# Protocell_module.net
KiCad netlist of a schematic drawn in EAGLE
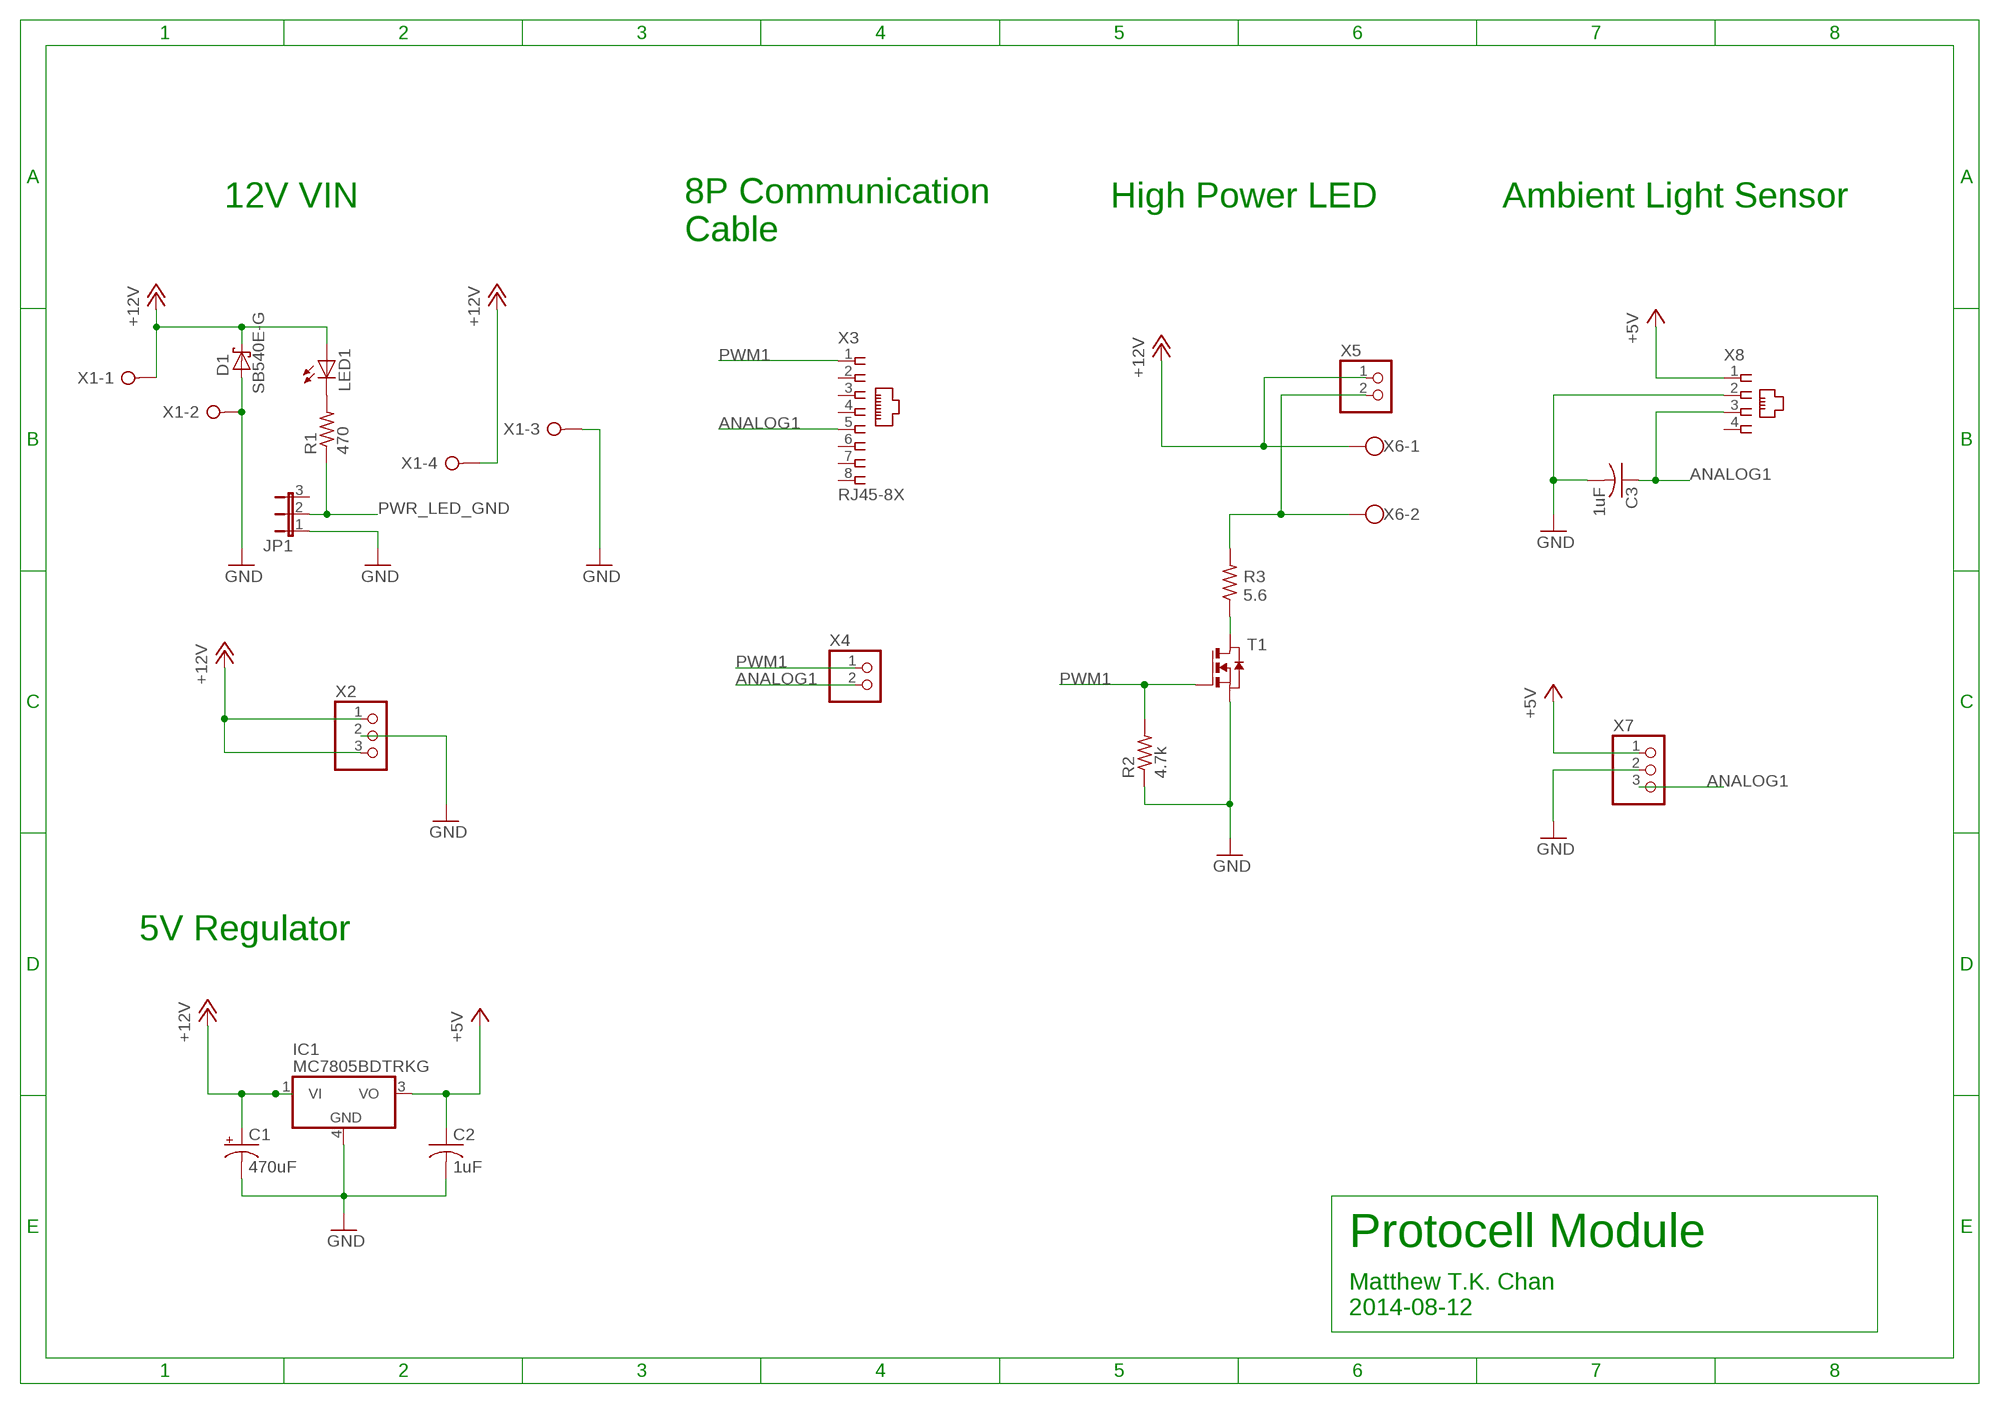
[diagram p0: schematic, sheet 1]

(export (version "E")
  (design (tool "Eeschema 10.0.6"))
  (components
    (comp (ref "C1")
      (value "470uF")
      (footprint "eagle-import:E5-10,5")
      (libsource (lib "eagle-import") (part "CPOL-USE5-10.5"))
    )
    (comp (ref "C2")
      (value "1uF")
      (footprint "eagle-import:C0603")
      (libsource (lib "eagle-import") (part "C-USC0603"))
    )
    (comp (ref "C3")
      (value "1uF")
      (footprint "eagle-import:C0603")
      (libsource (lib "eagle-import") (part "C-USC0603"))
    )
    (comp (ref "D1")
      (value "SB540E-G")
      (footprint "eagle-import:DO201T15")
      (libsource (lib "eagle-import") (part "SB540E-G"))
    )
    (comp (ref "IC1")
      (value "MC7805BDTRKG")
      (footprint "eagle-import:DPACK_3")
      (libsource (lib "eagle-import") (part "MC7805BDTRKG"))
    )
    (comp (ref "JP1")
      (value "JP2E")
      (footprint "eagle-import:JP2")
      (libsource (lib "eagle-import") (part "JP2E"))
    )
    (comp (ref "LED1")
      (value "LEDSML1206")
      (footprint "eagle-import:SML1206")
      (libsource (lib "eagle-import") (part "LEDSML1206"))
    )
    (comp (ref "R1")
      (value "470")
      (footprint "eagle-import:R0603")
      (libsource (lib "eagle-import") (part "R-US_R0603"))
    )
    (comp (ref "R2")
      (value "4.7k")
      (footprint "eagle-import:R0603")
      (libsource (lib "eagle-import") (part "R-US_R0603"))
    )
    (comp (ref "R3")
      (value "5.6")
      (footprint "eagle-import:YAGEO_SQP500JB")
      (libsource (lib "eagle-import") (part "SQP500JB-5R6"))
    )
    (comp (ref "T1")
      (value "NTD5867NLT4G")
      (footprint "eagle-import:DPACK")
      (libsource (lib "eagle-import") (part "NTD5867NLT4G"))
    )
    (comp (ref "X1")
      (value "W237-04P")
      (footprint "eagle-import:W237-4P")
      (libsource (lib "eagle-import") (part "W237-04P"))
    )
    (comp (ref "X2")
      (value "PINHD-1X3/90")
      (footprint "eagle-import:1X03_90")
      (libsource (lib "eagle-import") (part "PINHD-1X3/90"))
    )
    (comp (ref "X3")
      (value "RJ45-8X")
      (footprint "eagle-import:RJ45-NO-SHIELD")
      (libsource (lib "eagle-import") (part "RJ45-8X"))
    )
    (comp (ref "X4")
      (value "PINHD-1X2/90")
      (footprint "eagle-import:1X02_90")
      (libsource (lib "eagle-import") (part "PINHD-1X2/90"))
    )
    (comp (ref "X5")
      (value "PINHD-1X2/90")
      (footprint "eagle-import:1X02_90")
      (libsource (lib "eagle-import") (part "PINHD-1X2/90"))
    )
    (comp (ref "X6")
      (value "W237-102")
      (footprint "eagle-import:W237-102")
      (fields (field (name "MPN") "237-102"))
      (libsource (lib "eagle-import") (part "W237-102"))
    )
    (comp (ref "X7")
      (value "PINHD-1X3/90")
      (footprint "eagle-import:1X03_90")
      (libsource (lib "eagle-import") (part "PINHD-1X3/90"))
    )
    (comp (ref "X8")
      (value "558872-1")
      (footprint "eagle-import:558872-1")
      (fields (field (name "MF") "TYCO ELECTRONICS") (field (name "MPN") "5558872-1"))
      (libsource (lib "eagle-import") (part "558872-1"))
    )
  )
  (nets
    (net (code "1") (name "+5V") (class "Default")
      (node (ref "C2") (pin "1") (pinfunction "1_1") (pintype "passive"))
      (node (ref "IC1") (pin "3") (pinfunction "VO_3") (pintype "passive"))
      (node (ref "X7") (pin "1") (pinfunction "1_1") (pintype "passive"))
      (node (ref "X8") (pin "1") (pinfunction "1_1") (pintype "passive"))
    )
    (net (code "2") (name "+12V") (class "Default")
      (node (ref "C1") (pin "+") (pinfunction "+_+") (pintype "passive"))
      (node (ref "D1") (pin "C") (pinfunction "C_C") (pintype "passive"))
      (node (ref "IC1") (pin "1") (pinfunction "VI_1") (pintype "input"))
      (node (ref "LED1") (pin "A") (pinfunction "A_A") (pintype "passive"))
      (node (ref "X1") (pin "1") (pinfunction "KL_1") (pintype "passive"))
      (node (ref "X1") (pin "4") (pinfunction "KL_4") (pintype "passive"))
      (node (ref "X2") (pin "1") (pinfunction "1_1") (pintype "passive"))
      (node (ref "X2") (pin "3") (pinfunction "3_3") (pintype "passive"))
      (node (ref "X5") (pin "1") (pinfunction "1_1") (pintype "passive"))
      (node (ref "X6") (pin "1") (pinfunction "KL_1") (pintype "passive"))
    )
    (net (code "3") (name "/ANALOG1") (class "Default")
      (node (ref "C3") (pin "1") (pinfunction "1_1") (pintype "passive"))
      (node (ref "X3") (pin "5") (pinfunction "5_5") (pintype "passive"))
      (node (ref "X4") (pin "2") (pinfunction "2_2") (pintype "passive"))
      (node (ref "X7") (pin "3") (pinfunction "3_3") (pintype "passive"))
      (node (ref "X8") (pin "3") (pinfunction "3_3") (pintype "passive"))
    )
    (net (code "4") (name "/PWM1") (class "Default")
      (node (ref "R2") (pin "2") (pinfunction "2_2") (pintype "passive"))
      (node (ref "T1") (pin "1") (pinfunction "G_1") (pintype "passive"))
      (node (ref "X3") (pin "1") (pinfunction "1_1") (pintype "passive"))
      (node (ref "X4") (pin "1") (pinfunction "1_1") (pintype "passive"))
    )
    (net (code "5") (name "/PWR_LED_GND") (class "Default")
      (node (ref "JP1") (pin "2") (pinfunction "2_2") (pintype "passive"))
      (node (ref "R1") (pin "1") (pinfunction "1_1") (pintype "passive"))
    )
    (net (code "6") (name "GND") (class "Default")
      (node (ref "C1") (pin "-") (pinfunction "-_-") (pintype "passive"))
      (node (ref "C2") (pin "2") (pinfunction "2_2") (pintype "passive"))
      (node (ref "C3") (pin "2") (pinfunction "2_2") (pintype "passive"))
      (node (ref "D1") (pin "A") (pinfunction "A_A") (pintype "passive"))
      (node (ref "IC1") (pin "4") (pinfunction "GND_4") (pintype "passive"))
      (node (ref "JP1") (pin "1") (pinfunction "1_1") (pintype "passive"))
      (node (ref "R2") (pin "1") (pinfunction "1_1") (pintype "passive"))
      (node (ref "T1") (pin "3") (pinfunction "S_3") (pintype "passive"))
      (node (ref "X1") (pin "2") (pinfunction "KL_2") (pintype "passive"))
      (node (ref "X1") (pin "3") (pinfunction "KL_3") (pintype "passive"))
      (node (ref "X2") (pin "2") (pinfunction "2_2") (pintype "passive"))
      (node (ref "X7") (pin "2") (pinfunction "2_2") (pintype "passive"))
      (node (ref "X8") (pin "2") (pinfunction "2_2") (pintype "passive"))
    )
    (net (code "7") (name "Net-(LED1-PadC)") (class "Default")
      (node (ref "LED1") (pin "C") (pinfunction "C_C") (pintype "passive"))
      (node (ref "R1") (pin "2") (pinfunction "2_2") (pintype "passive"))
    )
    (net (code "8") (name "Net-(T1-D)") (class "Default")
      (node (ref "R3") (pin "1") (pinfunction "1_1") (pintype "passive"))
      (node (ref "T1") (pin "2") (pinfunction "D_2") (pintype "passive"))
    )
    (net (code "9") (name "Net-(X6B-KL)") (class "Default")
      (node (ref "R3") (pin "2") (pinfunction "2_2") (pintype "passive"))
      (node (ref "X5") (pin "2") (pinfunction "2_2") (pintype "passive"))
      (node (ref "X6") (pin "2") (pinfunction "KL_2") (pintype "passive"))
    )
    (net (code "10") (name "unconnected-(JP1-Pad3)") (class "Default")
      (node (ref "JP1") (pin "3") (pinfunction "3_3") (pintype "passive"))
    )
    (net (code "11") (name "unconnected-(X3-Pad2)") (class "Default")
      (node (ref "X3") (pin "2") (pinfunction "2_2") (pintype "passive"))
    )
    (net (code "12") (name "unconnected-(X3-Pad3)") (class "Default")
      (node (ref "X3") (pin "3") (pinfunction "3_3") (pintype "passive"))
    )
    (net (code "13") (name "unconnected-(X3-Pad4)") (class "Default")
      (node (ref "X3") (pin "4") (pinfunction "4_4") (pintype "passive"))
    )
    (net (code "14") (name "unconnected-(X3-Pad6)") (class "Default")
      (node (ref "X3") (pin "6") (pinfunction "6_6") (pintype "passive"))
    )
    (net (code "15") (name "unconnected-(X3-Pad7)") (class "Default")
      (node (ref "X3") (pin "7") (pinfunction "7_7") (pintype "passive"))
    )
    (net (code "16") (name "unconnected-(X3-Pad8)") (class "Default")
      (node (ref "X3") (pin "8") (pinfunction "8_8") (pintype "passive"))
    )
    (net (code "17") (name "unconnected-(X8-Pad4)") (class "Default")
      (node (ref "X8") (pin "4") (pinfunction "4_4") (pintype "passive"))
    )
  )
)
